# Frank.net
KiCad netlist of a schematic drawn in EAGLE
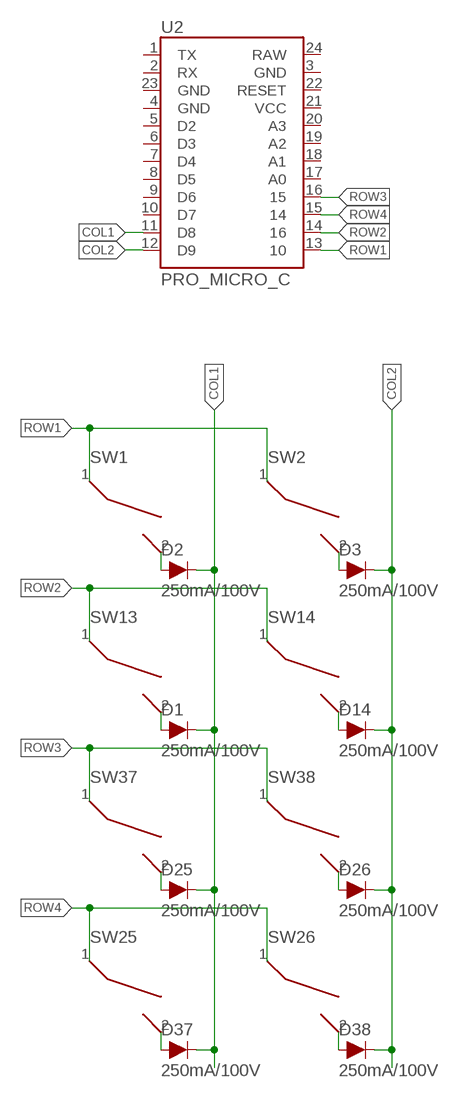
[diagram p0: schematic, sheet 1]

(export (version "E")
  (design (tool "Eeschema 10.0.6"))
  (components
    (comp (ref "D1")
      (value "250mA/100V")
      (footprint "eagle-import:SOD-323")
      (libsource (lib "eagle-import") (part "DIODE-BAS16J"))
    )
    (comp (ref "D2")
      (value "250mA/100V")
      (footprint "eagle-import:SOD-323")
      (libsource (lib "eagle-import") (part "DIODE-BAS16J"))
    )
    (comp (ref "D3")
      (value "250mA/100V")
      (footprint "eagle-import:SOD-323")
      (libsource (lib "eagle-import") (part "DIODE-BAS16J"))
    )
    (comp (ref "D14")
      (value "250mA/100V")
      (footprint "eagle-import:SOD-323")
      (libsource (lib "eagle-import") (part "DIODE-BAS16J"))
    )
    (comp (ref "D25")
      (value "250mA/100V")
      (footprint "eagle-import:SOD-323")
      (libsource (lib "eagle-import") (part "DIODE-BAS16J"))
    )
    (comp (ref "D26")
      (value "250mA/100V")
      (footprint "eagle-import:SOD-323")
      (libsource (lib "eagle-import") (part "DIODE-BAS16J"))
    )
    (comp (ref "D37")
      (value "250mA/100V")
      (footprint "eagle-import:SOD-323")
      (libsource (lib "eagle-import") (part "DIODE-BAS16J"))
    )
    (comp (ref "D38")
      (value "250mA/100V")
      (footprint "eagle-import:SOD-323")
      (libsource (lib "eagle-import") (part "DIODE-BAS16J"))
    )
    (comp (ref "SW1")
      (value "CHERRY_MX_WITH_FIXING_PINS")
      (footprint "eagle-import:MX1A-XXNW")
      (libsource (lib "eagle-import") (part "CHERRY_MX_WITH_FIXING_PINS"))
    )
    (comp (ref "SW2")
      (value "CHERRY_MX_WITH_FIXING_PINS")
      (footprint "eagle-import:MX1A-XXNW")
      (libsource (lib "eagle-import") (part "CHERRY_MX_WITH_FIXING_PINS"))
    )
    (comp (ref "SW13")
      (value "CHERRY_MX_WITH_FIXING_PINS")
      (footprint "eagle-import:MX1A-XXNW")
      (libsource (lib "eagle-import") (part "CHERRY_MX_WITH_FIXING_PINS"))
    )
    (comp (ref "SW14")
      (value "CHERRY_MX_WITH_FIXING_PINS")
      (footprint "eagle-import:MX1A-XXNW")
      (libsource (lib "eagle-import") (part "CHERRY_MX_WITH_FIXING_PINS"))
    )
    (comp (ref "SW25")
      (value "CHERRY_MX_WITH_FIXING_PINS")
      (footprint "eagle-import:MX1A-XXNW")
      (libsource (lib "eagle-import") (part "CHERRY_MX_WITH_FIXING_PINS"))
    )
    (comp (ref "SW26")
      (value "CHERRY_MX_WITH_FIXING_PINS")
      (footprint "eagle-import:MX1A-XXNW")
      (libsource (lib "eagle-import") (part "CHERRY_MX_WITH_FIXING_PINS"))
    )
    (comp (ref "SW37")
      (value "CHERRY_MX_WITH_FIXING_PINS")
      (footprint "eagle-import:MX1A-XXNW")
      (libsource (lib "eagle-import") (part "CHERRY_MX_WITH_FIXING_PINS"))
    )
    (comp (ref "SW38")
      (value "CHERRY_MX_WITH_FIXING_PINS")
      (footprint "eagle-import:MX1A-XXNW")
      (libsource (lib "eagle-import") (part "CHERRY_MX_WITH_FIXING_PINS"))
    )
    (comp (ref "U2")
      (value "PRO_MICRO_C")
      (footprint "eagle-import:PRO_MICRO_C")
      (libsource (lib "eagle-import") (part "PRO_MICRO_C"))
    )
  )
  (nets
    (net (code "1") (name "COL1") (class "Default")
      (node (ref "D1") (pin "C") (pinfunction "C_C") (pintype "passive"))
      (node (ref "D2") (pin "C") (pinfunction "C_C") (pintype "passive"))
      (node (ref "D25") (pin "C") (pinfunction "C_C") (pintype "passive"))
      (node (ref "D37") (pin "C") (pinfunction "C_C") (pintype "passive"))
      (node (ref "U2") (pin "11") (pinfunction "D8_11") (pintype "bidirectional"))
    )
    (net (code "2") (name "COL2") (class "Default")
      (node (ref "D14") (pin "C") (pinfunction "C_C") (pintype "passive"))
      (node (ref "D26") (pin "C") (pinfunction "C_C") (pintype "passive"))
      (node (ref "D3") (pin "C") (pinfunction "C_C") (pintype "passive"))
      (node (ref "D38") (pin "C") (pinfunction "C_C") (pintype "passive"))
      (node (ref "U2") (pin "12") (pinfunction "D9_12") (pintype "bidirectional"))
    )
    (net (code "3") (name "Net-(D1-PadA)") (class "Default")
      (node (ref "D1") (pin "A") (pinfunction "A_A") (pintype "passive"))
      (node (ref "SW13") (pin "2") (pinfunction "2_2") (pintype "passive"))
    )
    (net (code "4") (name "Net-(D2-PadA)") (class "Default")
      (node (ref "D2") (pin "A") (pinfunction "A_A") (pintype "passive"))
      (node (ref "SW1") (pin "2") (pinfunction "2_2") (pintype "passive"))
    )
    (net (code "5") (name "Net-(D3-PadA)") (class "Default")
      (node (ref "D3") (pin "A") (pinfunction "A_A") (pintype "passive"))
      (node (ref "SW2") (pin "2") (pinfunction "2_2") (pintype "passive"))
    )
    (net (code "6") (name "Net-(D14-PadA)") (class "Default")
      (node (ref "D14") (pin "A") (pinfunction "A_A") (pintype "passive"))
      (node (ref "SW14") (pin "2") (pinfunction "2_2") (pintype "passive"))
    )
    (net (code "7") (name "Net-(D25-PadA)") (class "Default")
      (node (ref "D25") (pin "A") (pinfunction "A_A") (pintype "passive"))
      (node (ref "SW37") (pin "2") (pinfunction "2_2") (pintype "passive"))
    )
    (net (code "8") (name "Net-(D26-PadA)") (class "Default")
      (node (ref "D26") (pin "A") (pinfunction "A_A") (pintype "passive"))
      (node (ref "SW38") (pin "2") (pinfunction "2_2") (pintype "passive"))
    )
    (net (code "9") (name "Net-(D37-PadA)") (class "Default")
      (node (ref "D37") (pin "A") (pinfunction "A_A") (pintype "passive"))
      (node (ref "SW25") (pin "2") (pinfunction "2_2") (pintype "passive"))
    )
    (net (code "10") (name "Net-(D38-PadA)") (class "Default")
      (node (ref "D38") (pin "A") (pinfunction "A_A") (pintype "passive"))
      (node (ref "SW26") (pin "2") (pinfunction "2_2") (pintype "passive"))
    )
    (net (code "11") (name "ROW1") (class "Default")
      (node (ref "SW1") (pin "1") (pinfunction "1_1") (pintype "passive"))
      (node (ref "SW2") (pin "1") (pinfunction "1_1") (pintype "passive"))
      (node (ref "U2") (pin "13") (pinfunction "10_13") (pintype "bidirectional"))
    )
    (net (code "12") (name "ROW2") (class "Default")
      (node (ref "SW13") (pin "1") (pinfunction "1_1") (pintype "passive"))
      (node (ref "SW14") (pin "1") (pinfunction "1_1") (pintype "passive"))
      (node (ref "U2") (pin "14") (pinfunction "16_14") (pintype "bidirectional"))
    )
    (net (code "13") (name "ROW3") (class "Default")
      (node (ref "SW37") (pin "1") (pinfunction "1_1") (pintype "passive"))
      (node (ref "SW38") (pin "1") (pinfunction "1_1") (pintype "passive"))
      (node (ref "U2") (pin "16") (pinfunction "15_16") (pintype "bidirectional"))
    )
    (net (code "14") (name "ROW4") (class "Default")
      (node (ref "SW25") (pin "1") (pinfunction "1_1") (pintype "passive"))
      (node (ref "SW26") (pin "1") (pinfunction "1_1") (pintype "passive"))
      (node (ref "U2") (pin "15") (pinfunction "14_15") (pintype "bidirectional"))
    )
    (net (code "15") (name "unconnected-(U2-A0-Pad17)") (class "Default")
      (node (ref "U2") (pin "17") (pinfunction "A0_17") (pintype "bidirectional"))
    )
    (net (code "16") (name "unconnected-(U2-A1-Pad18)") (class "Default")
      (node (ref "U2") (pin "18") (pinfunction "A1_18") (pintype "bidirectional"))
    )
    (net (code "17") (name "unconnected-(U2-A2-Pad19)") (class "Default")
      (node (ref "U2") (pin "19") (pinfunction "A2_19") (pintype "bidirectional"))
    )
    (net (code "18") (name "unconnected-(U2-A3-Pad20)") (class "Default")
      (node (ref "U2") (pin "20") (pinfunction "A3_20") (pintype "bidirectional"))
    )
    (net (code "19") (name "unconnected-(U2-D2-Pad5)") (class "Default")
      (node (ref "U2") (pin "5") (pinfunction "D2_5") (pintype "bidirectional"))
    )
    (net (code "20") (name "unconnected-(U2-D3-Pad6)") (class "Default")
      (node (ref "U2") (pin "6") (pinfunction "D3_6") (pintype "bidirectional"))
    )
    (net (code "21") (name "unconnected-(U2-D4-Pad7)") (class "Default")
      (node (ref "U2") (pin "7") (pinfunction "D4_7") (pintype "bidirectional"))
    )
    (net (code "22") (name "unconnected-(U2-D5-Pad8)") (class "Default")
      (node (ref "U2") (pin "8") (pinfunction "D5_8") (pintype "bidirectional"))
    )
    (net (code "23") (name "unconnected-(U2-D6-Pad9)") (class "Default")
      (node (ref "U2") (pin "9") (pinfunction "D6_9") (pintype "bidirectional"))
    )
    (net (code "24") (name "unconnected-(U2-D7-Pad10)") (class "Default")
      (node (ref "U2") (pin "10") (pinfunction "D7_10") (pintype "bidirectional"))
    )
    (net (code "25") (name "unconnected-(U2-GND-Pad3)") (class "Default")
      (node (ref "U2") (pin "3") (pinfunction "GND_3") (pintype "bidirectional"))
    )
    (net (code "26") (name "unconnected-(U2-GND-Pad4)") (class "Default")
      (node (ref "U2") (pin "4") (pinfunction "GND_4") (pintype "bidirectional"))
    )
    (net (code "27") (name "unconnected-(U2-GND-Pad23)") (class "Default")
      (node (ref "U2") (pin "23") (pinfunction "GND_23") (pintype "bidirectional"))
    )
    (net (code "28") (name "unconnected-(U2-RAW-Pad24)") (class "Default")
      (node (ref "U2") (pin "24") (pinfunction "RAW_24") (pintype "bidirectional"))
    )
    (net (code "29") (name "unconnected-(U2-RESET-Pad22)") (class "Default")
      (node (ref "U2") (pin "22") (pinfunction "RESET_22") (pintype "bidirectional"))
    )
    (net (code "30") (name "unconnected-(U2-RX-Pad2)") (class "Default")
      (node (ref "U2") (pin "2") (pinfunction "RX_2") (pintype "bidirectional"))
    )
    (net (code "31") (name "unconnected-(U2-TX-Pad1)") (class "Default")
      (node (ref "U2") (pin "1") (pinfunction "TX_1") (pintype "bidirectional"))
    )
    (net (code "32") (name "unconnected-(U2-VCC-Pad21)") (class "Default")
      (node (ref "U2") (pin "21") (pinfunction "VCC_21") (pintype "bidirectional"))
    )
  )
)
